# 3V3_LDO.net
KiCad netlist of a schematic drawn in Altium Designer
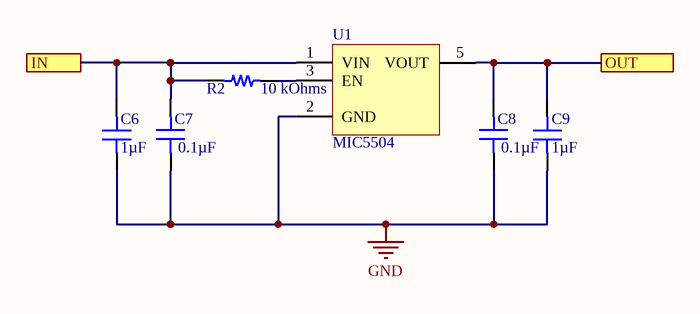
[diagram p0: 3V3_LDO.SchDoc]

(export (version "E")
  (design (tool "Eeschema 10.0.6"))
  (components
    (comp (ref "C6")
      (value "1µF")
      (footprint "CAP 0603_1608")
      (description "CAP CER 1UF 25V X7R 0603")
      (fields
        (field (name "PART NUMBER") "GCJ188R71E105KA01D")
        (field (name "MANUFACTURER") "Murata Electronics")
      )
      (libsource (lib "Celestial Altium Library - altium_library") (part "Capacitor"))
    )
    (comp (ref "C7")
      (value "0.1µF")
      (footprint "CAP 0603_1608")
      (description "CAP CER 0.1UF 100V 0603 EPOXY")
      (fields
        (field (name "PART NUMBER") "GCG188R92A104KA03D")
        (field (name "MANUFACTURER") "Murata Electronics")
      )
      (libsource (lib "Celestial Altium Library - altium_library") (part "Capacitor"))
    )
    (comp (ref "C8")
      (value "0.1µF")
      (footprint "CAP 0603_1608")
      (description "CAP CER 0.1UF 100V 0603 EPOXY")
      (fields
        (field (name "PART NUMBER") "GCG188R92A104KA03D")
        (field (name "MANUFACTURER") "Murata Electronics")
      )
      (libsource (lib "Celestial Altium Library - altium_library") (part "Capacitor"))
    )
    (comp (ref "C9")
      (value "1µF")
      (footprint "CAP 0603_1608")
      (description "CAP CER 1UF 25V X7R 0603")
      (fields
        (field (name "PART NUMBER") "GCJ188R71E105KA01D")
        (field (name "MANUFACTURER") "Murata Electronics")
      )
      (libsource (lib "Celestial Altium Library - altium_library") (part "Capacitor"))
    )
    (comp (ref "R2")
      (value "10 kOhms")
      (footprint "RES 0603_1608")
      (description "RES 10K OHM 0.1% 1/16W 0603")
      (fields
        (field (name "PART NUMBER") "RNCS0603BKE10K0")
        (field (name "MANUFACTURER") "Stackpole Electronics Inc")
      )
      (libsource (lib "Celestial Altium Library - altium_library") (part "Resistor"))
    )
    (comp (ref "U1")
      (value "MIC5504")
      (footprint "TI SOT-23-5 DBV")
      (description "3.3V LDO")
      (libsource (lib "IC") (part "MIC5504-3.3YM5"))
    )
  )
  (nets
    (net (code "1") (name "/IN") (class "Default")
      (node (ref "C6") (pin "2") (pinfunction "2_2") (pintype "passive"))
      (node (ref "C7") (pin "1") (pinfunction "1_1") (pintype "passive"))
      (node (ref "R2") (pin "2") (pinfunction "2_2") (pintype "passive"))
      (node (ref "U1") (pin "1") (pinfunction "VIN_1") (pintype "passive"))
    )
    (net (code "2") (name "/OUT") (class "Default")
      (node (ref "C8") (pin "1") (pinfunction "1_1") (pintype "passive"))
      (node (ref "C9") (pin "2") (pinfunction "2_2") (pintype "passive"))
      (node (ref "U1") (pin "5") (pinfunction "VOUT_5") (pintype "passive"))
    )
    (net (code "3") (name "GND") (class "Default")
      (node (ref "C6") (pin "1") (pinfunction "1_1") (pintype "passive"))
      (node (ref "C7") (pin "2") (pinfunction "2_2") (pintype "passive"))
      (node (ref "C8") (pin "2") (pinfunction "2_2") (pintype "passive"))
      (node (ref "C9") (pin "1") (pinfunction "1_1") (pintype "passive"))
      (node (ref "U1") (pin "2") (pinfunction "GND_2") (pintype "passive"))
    )
    (net (code "4") (name "Net-(U1-EN)") (class "Default")
      (node (ref "R2") (pin "1") (pinfunction "1_1") (pintype "passive"))
      (node (ref "U1") (pin "3") (pinfunction "EN_3") (pintype "passive"))
    )
  )
)
